# LCD.net
KiCad netlist of a schematic drawn in Altium Designer
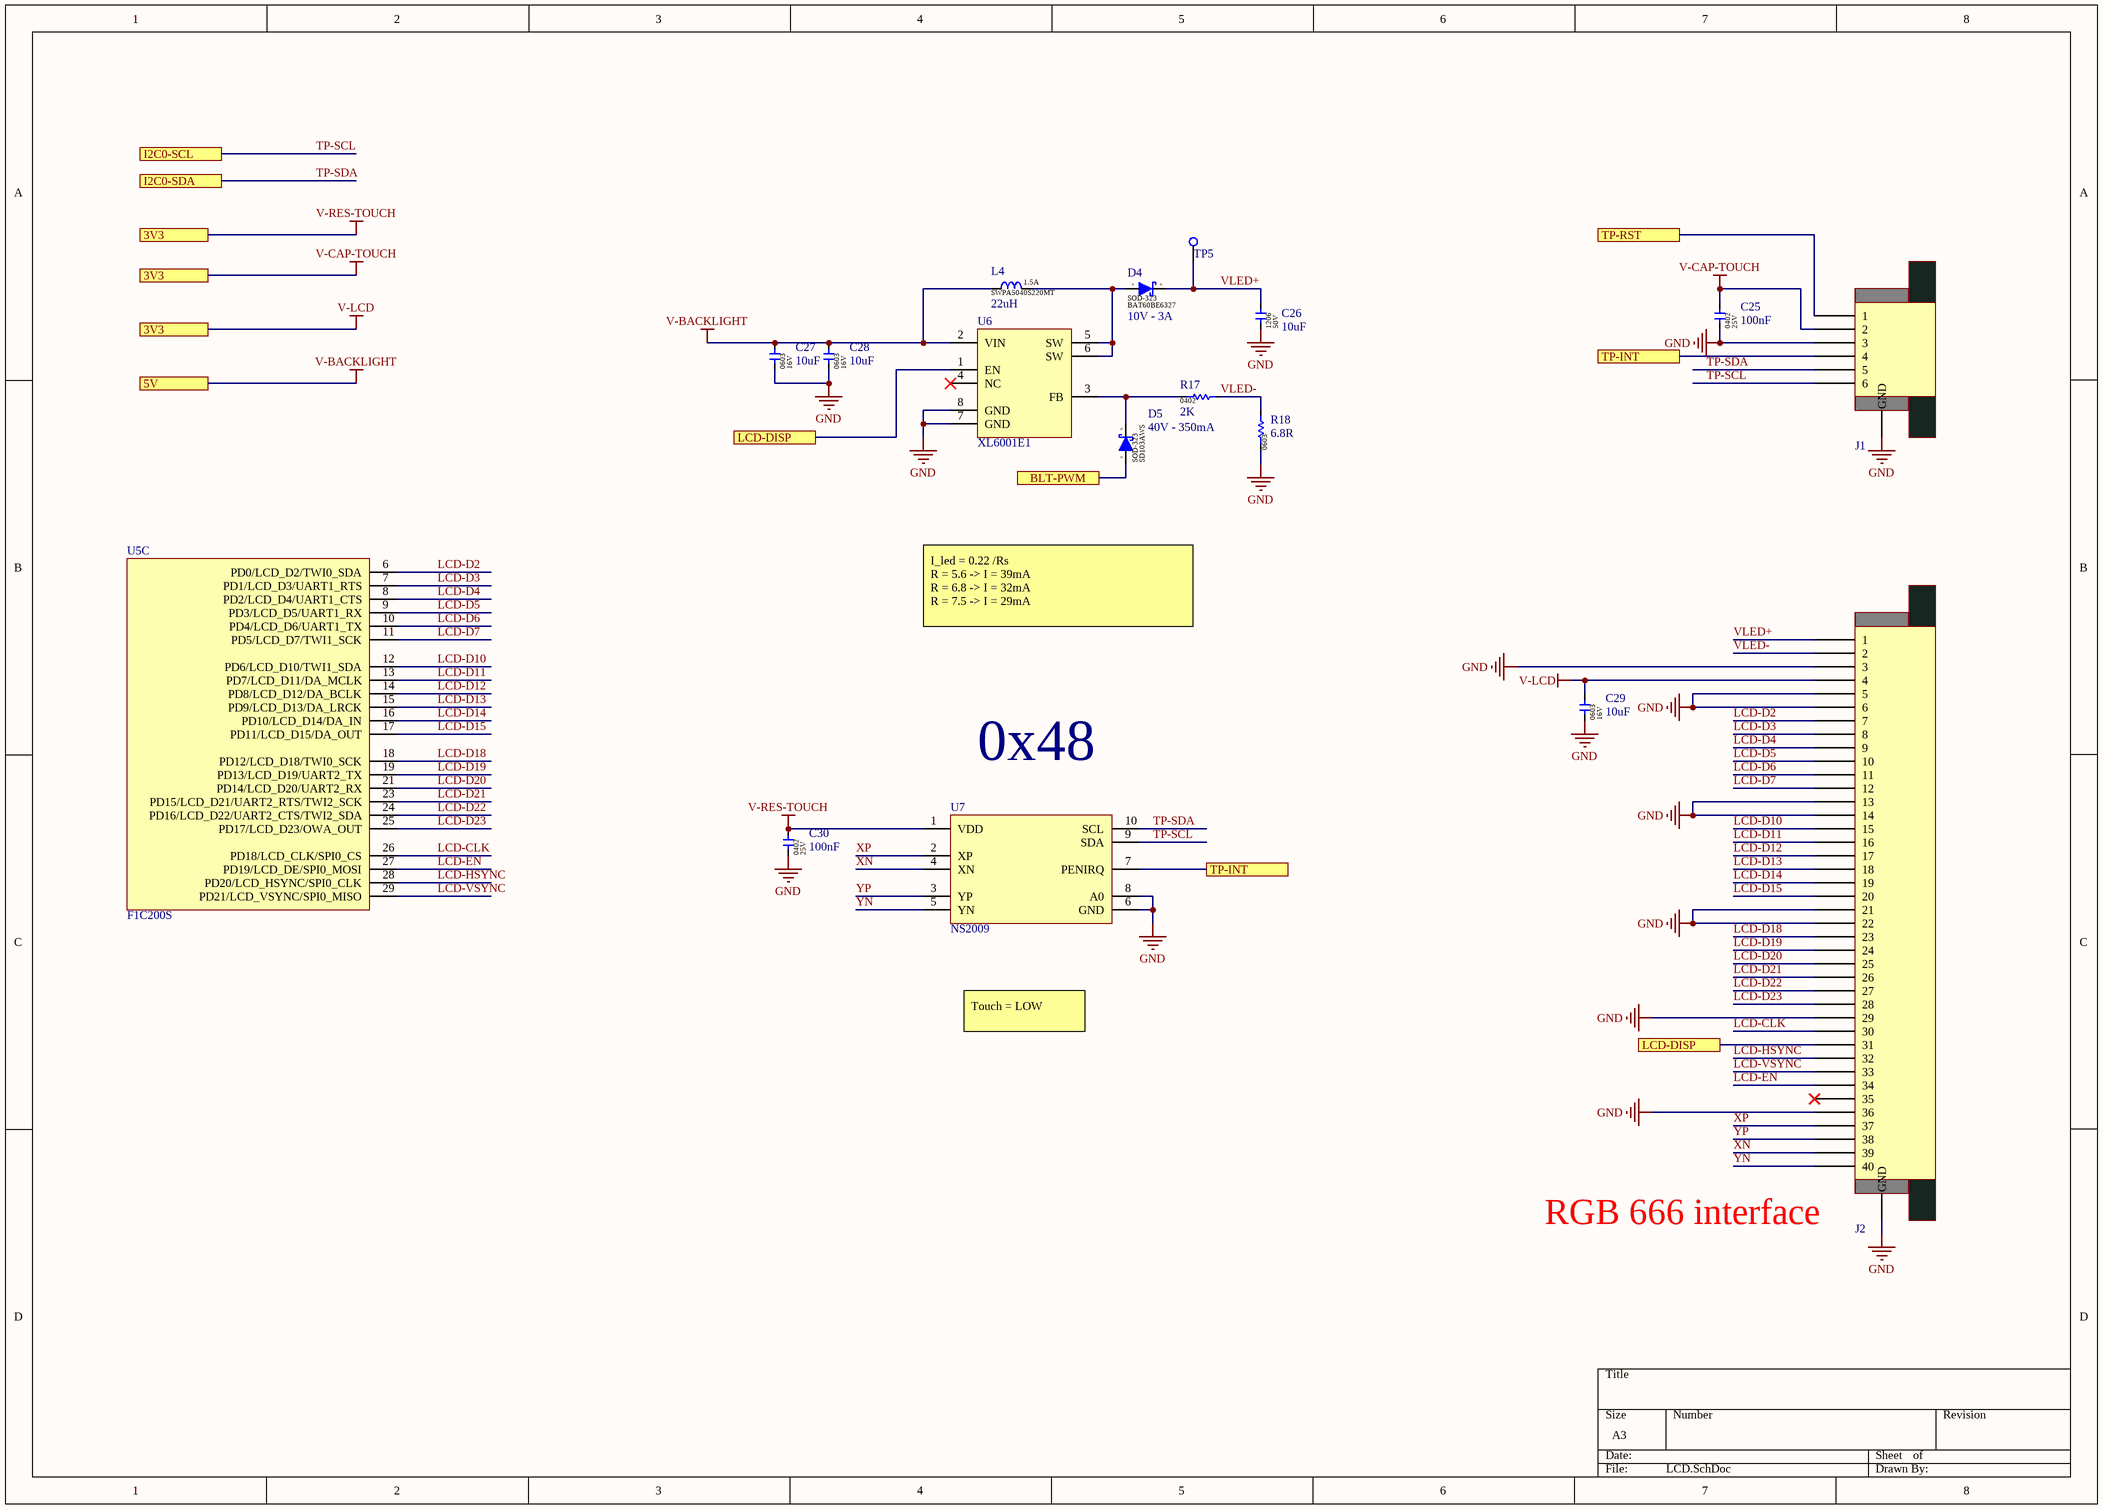
[diagram p0: LCD.SchDoc]

(export (version "E")
  (design (tool "Eeschema 10.0.6"))
  (components
    (comp (ref "C25")
      (value "100nF")
      (footprint "CAP-0402")
      (description "100nF ±10% 25V X5R 0402 Multilayer Ceramic Capacitors MLCC - SMD/SMT RoHS")
      (fields (field (name "MANUFACTURE PART") "0402X104K250CT") (field (name "VOLTAGE") "25V"))
      (libsource (lib "Capacitor Database") (part "Cap-non-polarized"))
    )
    (comp (ref "C26")
      (value "10uF")
      (footprint "CAP-1206")
      (description "10uF ±10% 50V X5R 1206 Multilayer Ceramic Capacitors MLCC - SMD/SMT RoHS")
      (fields (field (name "MANUFACTURE PART") "1206X106K500CT") (field (name "VOLTAGE") "50V"))
      (libsource (lib "Capacitor Database") (part "Cap-non-polarized"))
    )
    (comp (ref "C27")
      (value "10uF")
      (footprint "CAP-0603")
      (description "16V 10uF X5R ±20% 0603 Multilayer Ceramic Capacitors MLCC - SMD/SMT ROHS")
      (fields (field (name "MANUFACTURE PART") "0603X106M160CT") (field (name "VOLTAGE") "16V"))
      (libsource (lib "Capacitor Database") (part "Cap-non-polarized"))
    )
    (comp (ref "C28")
      (value "10uF")
      (footprint "CAP-0603")
      (description "16V 10uF X5R ±20% 0603 Multilayer Ceramic Capacitors MLCC - SMD/SMT ROHS")
      (fields (field (name "MANUFACTURE PART") "0603X106M160CT") (field (name "VOLTAGE") "16V"))
      (libsource (lib "Capacitor Database") (part "Cap-non-polarized"))
    )
    (comp (ref "C29")
      (value "10uF")
      (footprint "CAP-0603")
      (description "16V 10uF X5R ±20% 0603 Multilayer Ceramic Capacitors MLCC - SMD/SMT ROHS")
      (fields (field (name "MANUFACTURE PART") "0603X106M160CT") (field (name "VOLTAGE") "16V"))
      (libsource (lib "Capacitor Database") (part "Cap-non-polarized"))
    )
    (comp (ref "C30")
      (value "100nF")
      (footprint "CAP-0402")
      (description "100nF ±10% 25V X5R 0402 Multilayer Ceramic Capacitors MLCC - SMD/SMT RoHS")
      (fields (field (name "MANUFACTURE PART") "0402X104K250CT") (field (name "VOLTAGE") "25V"))
      (libsource (lib "Capacitor Database") (part "Cap-non-polarized"))
    )
    (comp (ref "D4")
      (value "10V - 3A")
      (footprint "SOD323 (UNI)")
      (description "10V 3A 600mV @ 1A SOD-323 Schottky Barrier Diodes (SBD) RoHS")
      (fields (field (name "MANUFACTURE PART") "BAT60BE6327"))
      (libsource (lib "Diode Database") (part "Schottky diode"))
    )
    (comp (ref "D5")
      (value "40V - 350mA")
      (footprint "SOD323 (UNI)")
      (description "40V 350mA 600mV @ 200mA SOD-323 Schottky Barrier Diodes (SBD) ROHS")
      (fields (field (name "MANUFACTURE PART") "SD103AWS"))
      (libsource (lib "Diode Database") (part "Schottky diode"))
    )
    (comp (ref "J1")
      (value "AFC07-S06ECC-00")
      (footprint "FPC - 6P, 0.5mm, top")
      (description "Slide Lock Contact,Top 6P FFC/FPC Connectors ROHS")
      (libsource (lib "Connectors, Misc") (part "FPC 0.5mm, 6P"))
    )
    (comp (ref "J2")
      (value "AFC07-S40ECC-00")
      (footprint "FPC - 40P, 0.5mm, top")
      (description "Contact,Top 40 0.020\"（0.50mm） 0.079\"（2.00mm） Slide Lock 40P FFC, FPC Connectors RoHS")
      (libsource (lib "Connectors, Misc") (part "FPC 0.5mm, 40P"))
    )
    (comp (ref "L4")
      (value "22uH")
      (footprint "IND-5040")
      (description "Inductor 22uH ±20% 1.5A, 5.0x5.0x4")
      (fields (field (name "MANUFACTURE PART") "SWPA5040S220MT"))
      (libsource (lib "Inductor Database") (part "Inductor"))
    )
    (comp (ref "R17")
      (value "2K")
      (footprint "RES-0402")
      (description "2kΩ ±1% 1/16W ±100ppm/℃ 0402 Chip Resistor - Surface Mount RoHS")
      (fields (field (name "MANUFACTURE PART") "WR04X2001FTL"))
      (libsource (lib "Resistor Database") (part "Resistor"))
    )
    (comp (ref "R18")
      (value "6.8R")
      (footprint "RES-0603")
      (description "6.8Ω ±1% ±1% 0.1W -200ppm/℃~+400ppm/℃ 0603 Chip Resistor - Surface Mount RoHS")
      (fields (field (name "MANUFACTURE PART") "WR06W6R80FTL"))
      (libsource (lib "Resistor Database") (part "Resistor"))
    )
    (comp (ref "TP5")
      (value "N/A")
      (footprint "Test point")
      (description "A point used for measure.")
      (libsource (lib "Connectors, Misc") (part "Test point"))
    )
    (comp (ref "U5")
      (value "F1C200S")
      (footprint "F1Cx00s")
      (description "The Allwinner F1C200s is a small SoC with an ARM926EJ-S CPU core and 64MB of embedded DDR SDRAM.")
      (libsource (lib "IC Database") (part "F1CX00S"))
    )
    (comp (ref "U6")
      (value "XL6001E1")
      (footprint "SOP-8")
      (description "SOIC-8_150mil LED Drivers RoHS")
      (libsource (lib "IC Database") (part "XL6001E1"))
    )
    (comp (ref "U7")
      (value "NS2009")
      (footprint "MSOP-10")
      (description "MSOP-10 Touch Screen Controllers RoHS")
      (libsource (lib "IC Database") (part "NS2009"))
    )
  )
  (nets
    (net (code "1") (name "/BLT-PWM") (class "Default")
      (node (ref "D5") (pin "2") (pinfunction "Anode_2") (pintype "passive"))
    )
    (net (code "2") (name "/LCD-CLK") (class "Default")
      (node (ref "J2") (pin "30") (pinfunction "30_30") (pintype "passive"))
      (node (ref "U5") (pin "26") (pinfunction "PD18/LCD_CLK/SPI0_CS_26") (pintype "passive"))
    )
    (net (code "3") (name "/LCD-D2") (class "Default")
      (node (ref "J2") (pin "7") (pinfunction "7_7") (pintype "passive"))
      (node (ref "U5") (pin "6") (pinfunction "PD0/LCD_D2/TWI0_SDA_6") (pintype "passive"))
    )
    (net (code "4") (name "/LCD-D3") (class "Default")
      (node (ref "J2") (pin "8") (pinfunction "8_8") (pintype "passive"))
      (node (ref "U5") (pin "7") (pinfunction "PD1/LCD_D3/UART1_RTS_7") (pintype "passive"))
    )
    (net (code "5") (name "/LCD-D4") (class "Default")
      (node (ref "J2") (pin "9") (pinfunction "9_9") (pintype "passive"))
      (node (ref "U5") (pin "8") (pinfunction "PD2/LCD_D4/UART1_CTS_8") (pintype "passive"))
    )
    (net (code "6") (name "/LCD-D5") (class "Default")
      (node (ref "J2") (pin "10") (pinfunction "10_10") (pintype "passive"))
      (node (ref "U5") (pin "9") (pinfunction "PD3/LCD_D5/UART1_RX_9") (pintype "passive"))
    )
    (net (code "7") (name "/LCD-D6") (class "Default")
      (node (ref "J2") (pin "11") (pinfunction "11_11") (pintype "passive"))
      (node (ref "U5") (pin "10") (pinfunction "PD4/LCD_D6/UART1_TX_10") (pintype "passive"))
    )
    (net (code "8") (name "/LCD-D7") (class "Default")
      (node (ref "J2") (pin "12") (pinfunction "12_12") (pintype "passive"))
      (node (ref "U5") (pin "11") (pinfunction "PD5/LCD_D7/TWI1_SCK_11") (pintype "passive"))
    )
    (net (code "9") (name "/LCD-D10") (class "Default")
      (node (ref "J2") (pin "15") (pinfunction "15_15") (pintype "passive"))
      (node (ref "U5") (pin "12") (pinfunction "PD6/LCD_D10/TWI1_SDA_12") (pintype "passive"))
    )
    (net (code "10") (name "/LCD-D11") (class "Default")
      (node (ref "J2") (pin "16") (pinfunction "16_16") (pintype "passive"))
      (node (ref "U5") (pin "13") (pinfunction "PD7/LCD_D11/DA_MCLK_13") (pintype "passive"))
    )
    (net (code "11") (name "/LCD-D12") (class "Default")
      (node (ref "J2") (pin "17") (pinfunction "17_17") (pintype "passive"))
      (node (ref "U5") (pin "14") (pinfunction "PD8/LCD_D12/DA_BCLK_14") (pintype "passive"))
    )
    (net (code "12") (name "/LCD-D13") (class "Default")
      (node (ref "J2") (pin "18") (pinfunction "18_18") (pintype "passive"))
      (node (ref "U5") (pin "15") (pinfunction "PD9/LCD_D13/DA_LRCK_15") (pintype "passive"))
    )
    (net (code "13") (name "/LCD-D14") (class "Default")
      (node (ref "J2") (pin "19") (pinfunction "19_19") (pintype "passive"))
      (node (ref "U5") (pin "16") (pinfunction "PD10/LCD_D14/DA_IN_16") (pintype "passive"))
    )
    (net (code "14") (name "/LCD-D15") (class "Default")
      (node (ref "J2") (pin "20") (pinfunction "20_20") (pintype "passive"))
      (node (ref "U5") (pin "17") (pinfunction "PD11/LCD_D15/DA_OUT_17") (pintype "passive"))
    )
    (net (code "15") (name "/LCD-D18") (class "Default")
      (node (ref "J2") (pin "23") (pinfunction "23_23") (pintype "passive"))
      (node (ref "U5") (pin "18") (pinfunction "PD12/LCD_D18/TWI0_SCK_18") (pintype "passive"))
    )
    (net (code "16") (name "/LCD-D19") (class "Default")
      (node (ref "J2") (pin "24") (pinfunction "24_24") (pintype "passive"))
      (node (ref "U5") (pin "19") (pinfunction "PD13/LCD_D19/UART2_TX_19") (pintype "passive"))
    )
    (net (code "17") (name "/LCD-D20") (class "Default")
      (node (ref "J2") (pin "25") (pinfunction "25_25") (pintype "passive"))
      (node (ref "U5") (pin "21") (pinfunction "PD14/LCD_D20/UART2_RX_21") (pintype "passive"))
    )
    (net (code "18") (name "/LCD-D21") (class "Default")
      (node (ref "J2") (pin "26") (pinfunction "26_26") (pintype "passive"))
      (node (ref "U5") (pin "23") (pinfunction "PD15/LCD_D21/UART2_RTS/TWI2_SCK_23") (pintype "passive"))
    )
    (net (code "19") (name "/LCD-D22") (class "Default")
      (node (ref "J2") (pin "27") (pinfunction "27_27") (pintype "passive"))
      (node (ref "U5") (pin "24") (pinfunction "PD16/LCD_D22/UART2_CTS/TWI2_SDA_24") (pintype "passive"))
    )
    (net (code "20") (name "/LCD-D23") (class "Default")
      (node (ref "J2") (pin "28") (pinfunction "28_28") (pintype "passive"))
      (node (ref "U5") (pin "25") (pinfunction "PD17/LCD_D23/OWA_OUT_25") (pintype "passive"))
    )
    (net (code "21") (name "/LCD-DISP") (class "Default")
      (node (ref "J2") (pin "31") (pinfunction "31_31") (pintype "passive"))
      (node (ref "U6") (pin "1") (pinfunction "EN_1") (pintype "passive"))
    )
    (net (code "22") (name "/LCD-EN") (class "Default")
      (node (ref "J2") (pin "34") (pinfunction "34_34") (pintype "passive"))
      (node (ref "U5") (pin "27") (pinfunction "PD19/LCD_DE/SPI0_MOSI_27") (pintype "passive"))
    )
    (net (code "23") (name "/LCD-HSYNC") (class "Default")
      (node (ref "J2") (pin "32") (pinfunction "32_32") (pintype "passive"))
      (node (ref "U5") (pin "28") (pinfunction "PD20/LCD_HSYNC/SPI0_CLK_28") (pintype "passive"))
    )
    (net (code "24") (name "/LCD-VSYNC") (class "Default")
      (node (ref "J2") (pin "33") (pinfunction "33_33") (pintype "passive"))
      (node (ref "U5") (pin "29") (pinfunction "PD21/LCD_VSYNC/SPI0_MISO_29") (pintype "passive"))
    )
    (net (code "25") (name "/TP-INT") (class "Default")
      (node (ref "J1") (pin "4") (pinfunction "4_4") (pintype "passive"))
      (node (ref "U7") (pin "7") (pinfunction "PENIRQ_7") (pintype "passive"))
    )
    (net (code "26") (name "/TP-RST") (class "Default")
      (node (ref "J1") (pin "1") (pinfunction "1_1") (pintype "passive"))
    )
    (net (code "27") (name "/TP-SCL") (class "Default")
      (node (ref "J1") (pin "6") (pinfunction "6_6") (pintype "passive"))
      (node (ref "U7") (pin "9") (pinfunction "SDA_9") (pintype "passive"))
    )
    (net (code "28") (name "/TP-SDA") (class "Default")
      (node (ref "J1") (pin "5") (pinfunction "5_5") (pintype "passive"))
      (node (ref "U7") (pin "10") (pinfunction "SCL_10") (pintype "passive"))
    )
    (net (code "29") (name "/VLED+") (class "Default")
      (node (ref "C26") (pin "2") (pinfunction "2_2") (pintype "passive"))
      (node (ref "D4") (pin "1") (pinfunction "Cathode_1") (pintype "passive"))
      (node (ref "J2") (pin "1") (pinfunction "1_1") (pintype "passive"))
      (node (ref "TP5") (pin "1") (pinfunction "1_1") (pintype "passive"))
    )
    (net (code "30") (name "/VLED-") (class "Default")
      (node (ref "J2") (pin "2") (pinfunction "2_2") (pintype "passive"))
      (node (ref "R17") (pin "2") (pinfunction "2_2") (pintype "passive"))
      (node (ref "R18") (pin "2") (pinfunction "2_2") (pintype "passive"))
    )
    (net (code "31") (name "/XN") (class "Default")
      (node (ref "J2") (pin "39") (pinfunction "39_39") (pintype "passive"))
      (node (ref "U7") (pin "4") (pinfunction "XN_4") (pintype "passive"))
    )
    (net (code "32") (name "/XP") (class "Default")
      (node (ref "J2") (pin "37") (pinfunction "37_37") (pintype "passive"))
      (node (ref "U7") (pin "2") (pinfunction "XP_2") (pintype "passive"))
    )
    (net (code "33") (name "/YN") (class "Default")
      (node (ref "J2") (pin "40") (pinfunction "40_40") (pintype "passive"))
      (node (ref "U7") (pin "5") (pinfunction "YN_5") (pintype "passive"))
    )
    (net (code "34") (name "/YP") (class "Default")
      (node (ref "J2") (pin "38") (pinfunction "38_38") (pintype "passive"))
      (node (ref "U7") (pin "3") (pinfunction "YP_3") (pintype "passive"))
    )
    (net (code "35") (name "GND") (class "Default")
      (node (ref "C25") (pin "1") (pinfunction "1_1") (pintype "passive"))
      (node (ref "C26") (pin "1") (pinfunction "1_1") (pintype "passive"))
      (node (ref "C27") (pin "1") (pinfunction "1_1") (pintype "passive"))
      (node (ref "C28") (pin "1") (pinfunction "1_1") (pintype "passive"))
      (node (ref "C29") (pin "1") (pinfunction "1_1") (pintype "passive"))
      (node (ref "C30") (pin "1") (pinfunction "1_1") (pintype "passive"))
      (node (ref "J1") (pin "0") (pinfunction "GND_0") (pintype "passive"))
      (node (ref "J1") (pin "3") (pinfunction "3_3") (pintype "passive"))
      (node (ref "J2") (pin "0") (pinfunction "GND_0") (pintype "passive"))
      (node (ref "J2") (pin "13") (pinfunction "13_13") (pintype "passive"))
      (node (ref "J2") (pin "14") (pinfunction "14_14") (pintype "passive"))
      (node (ref "J2") (pin "21") (pinfunction "21_21") (pintype "passive"))
      (node (ref "J2") (pin "22") (pinfunction "22_22") (pintype "passive"))
      (node (ref "J2") (pin "29") (pinfunction "29_29") (pintype "passive"))
      (node (ref "J2") (pin "3") (pinfunction "3_3") (pintype "passive"))
      (node (ref "J2") (pin "36") (pinfunction "36_36") (pintype "passive"))
      (node (ref "J2") (pin "5") (pinfunction "5_5") (pintype "passive"))
      (node (ref "J2") (pin "6") (pinfunction "6_6") (pintype "passive"))
      (node (ref "R18") (pin "1") (pinfunction "1_1") (pintype "passive"))
      (node (ref "U6") (pin "7") (pinfunction "GND_7") (pintype "passive"))
      (node (ref "U6") (pin "8") (pinfunction "GND_8") (pintype "passive"))
      (node (ref "U7") (pin "6") (pinfunction "GND_6") (pintype "passive"))
      (node (ref "U7") (pin "8") (pinfunction "A0_8") (pintype "passive"))
    )
    (net (code "36") (name "Net-(D4-Anode)") (class "Default")
      (node (ref "D4") (pin "2") (pinfunction "Anode_2") (pintype "passive"))
      (node (ref "L4") (pin "2") (pinfunction "2_2") (pintype "passive"))
      (node (ref "U6") (pin "5") (pinfunction "SW_5") (pintype "passive"))
      (node (ref "U6") (pin "6") (pinfunction "SW_6") (pintype "passive"))
    )
    (net (code "37") (name "Net-(D5-Cathode)") (class "Default")
      (node (ref "D5") (pin "1") (pinfunction "Cathode_1") (pintype "passive"))
      (node (ref "R17") (pin "1") (pinfunction "1_1") (pintype "passive"))
      (node (ref "U6") (pin "3") (pinfunction "FB_3") (pintype "passive"))
    )
    (net (code "38") (name "V-BACKLIGHT") (class "Default")
      (node (ref "C27") (pin "2") (pinfunction "2_2") (pintype "passive"))
      (node (ref "C28") (pin "2") (pinfunction "2_2") (pintype "passive"))
      (node (ref "L4") (pin "1") (pinfunction "1_1") (pintype "passive"))
      (node (ref "U6") (pin "2") (pinfunction "VIN_2") (pintype "passive"))
    )
    (net (code "39") (name "V-CAP-TOUCH") (class "Default")
      (node (ref "C25") (pin "2") (pinfunction "2_2") (pintype "passive"))
      (node (ref "C29") (pin "2") (pinfunction "2_2") (pintype "passive"))
      (node (ref "C30") (pin "2") (pinfunction "2_2") (pintype "passive"))
      (node (ref "J1") (pin "2") (pinfunction "2_2") (pintype "passive"))
      (node (ref "J2") (pin "4") (pinfunction "4_4") (pintype "passive"))
      (node (ref "U7") (pin "1") (pinfunction "VDD_1") (pintype "passive"))
    )
    (net (code "40") (name "unconnected-(J2-Pad35)") (class "Default")
      (node (ref "J2") (pin "35") (pinfunction "35_35") (pintype "passive+no_connect"))
    )
    (net (code "41") (name "unconnected-(U6-NC-Pad4)") (class "Default")
      (node (ref "U6") (pin "4") (pinfunction "NC_4") (pintype "passive+no_connect"))
    )
  )
)
